# Top.net
KiCad netlist of a schematic drawn in Altium Designer
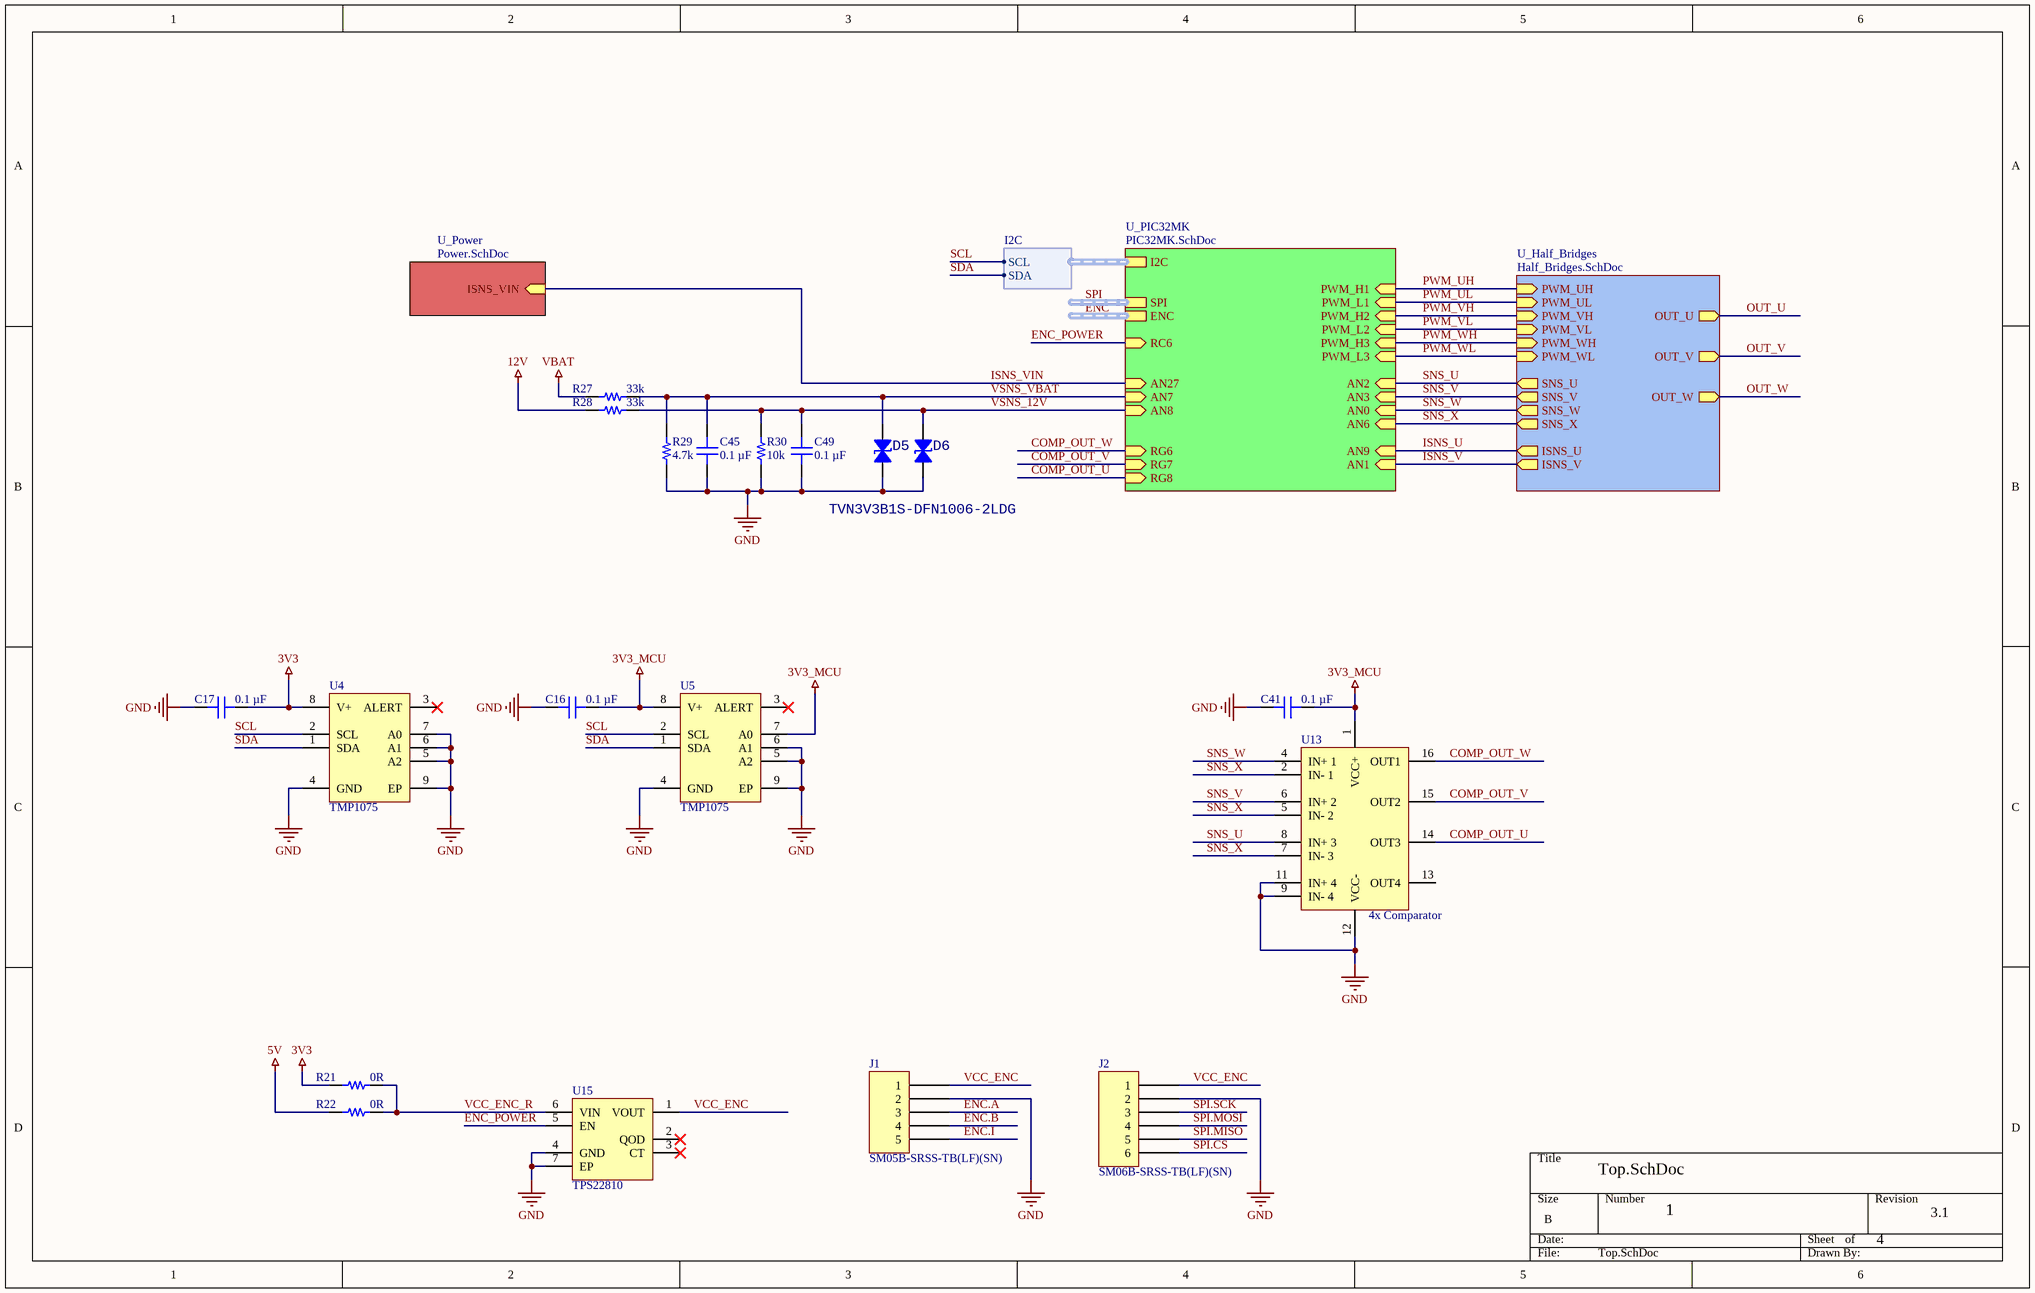
[diagram p0: Top.SchDoc]

(export (version "E")
  (design (tool "Eeschema 10.0.6"))
  (components
    (comp (ref "C16")
      (value "0.1 µF")
      (footprint "CAP 0402_1005")
      (description "CAP CER 0.1UF 16V X7R 0402")
      (fields (field (name "PART NUMBER") "C0402C104K4RACAUTO") (field (name "MANUFACTURER") "KEMET"))
      (libsource (lib "Celestial Altium Library - altium_library") (part "Capacitor"))
    )
    (comp (ref "C17")
      (value "0.1 µF")
      (footprint "CAP 0402_1005")
      (description "CAP CER 0.1UF 16V X7R 0402")
      (fields (field (name "PART NUMBER") "C0402C104K4RACAUTO") (field (name "MANUFACTURER") "KEMET"))
      (libsource (lib "Celestial Altium Library - altium_library") (part "Capacitor"))
    )
    (comp (ref "C41")
      (value "0.1 µF")
      (footprint "CAP 0402_1005")
      (description "CAP CER 0.1UF 16V X7R 0402")
      (fields (field (name "PART NUMBER") "C0402C104K4RACAUTO") (field (name "MANUFACTURER") "KEMET"))
      (libsource (lib "Celestial Altium Library - altium_library") (part "Capacitor"))
    )
    (comp (ref "C45")
      (value "0.1 µF")
      (footprint "CAP 0402_1005")
      (description "CAP CER 0.1UF 16V X7R 0402")
      (fields (field (name "PART NUMBER") "C0402C104K4RACAUTO") (field (name "MANUFACTURER") "KEMET"))
      (libsource (lib "Celestial Altium Library - altium_library") (part "Capacitor"))
    )
    (comp (ref "C49")
      (value "0.1 µF")
      (footprint "CAP 0402_1005")
      (description "CAP CER 0.1UF 16V X7R 0402")
      (fields (field (name "PART NUMBER") "C0402C104K4RACAUTO") (field (name "MANUFACTURER") "KEMET"))
      (libsource (lib "Celestial Altium Library - altium_library") (part "Capacitor"))
    )
    (comp (ref "D5")
      (value "TVN3V3B1S-DFN1006-2LDG")
      (footprint "0402")
      (description "TVS DIODE 3.3V 14.2PF DFN1006")
      (fields (field (name "MANUFACTURER") "INPAQ Technology Co., Ltd"))
      (libsource (lib "Celestial Altium Library - altium_library") (part "Diode TVS"))
    )
    (comp (ref "D6")
      (value "TVN3V3B1S-DFN1006-2LDG")
      (footprint "0402")
      (description "TVS DIODE 3.3V 14.2PF DFN1006")
      (fields (field (name "MANUFACTURER") "INPAQ Technology Co., Ltd"))
      (libsource (lib "Celestial Altium Library - altium_library") (part "Diode TVS"))
    )
    (comp (ref "J1")
      (value "SM05B-SRSS-TB(LF)(SN)")
      (footprint "JST SM05B-SRSS-TB")
      (description "CONN HEADER SMD R/A 5POS 1MM")
      (fields (field (name "MANUFACTURER") "JST Sales America Inc."))
      (libsource (lib "Celestial Altium Library - altium_library") (part "5 Pin"))
    )
    (comp (ref "J2")
      (value "SM06B-SRSS-TB(LF)(SN)")
      (footprint "JST SM06B-SRSS-TB")
      (description "CONN HEADER SMD R/A 6POS 1MM")
      (fields (field (name "MANUFACTURER") "JST Sales America Inc."))
      (libsource (lib "Celestial Altium Library - altium_library") (part "6 Pin"))
    )
    (comp (ref "R21")
      (value "0R")
      (footprint "RES_0402")
      (description "RES 0402")
      (libsource (lib "IC") (part "RES_0402"))
    )
    (comp (ref "R22")
      (value "0R")
      (footprint "RES_0402")
      (description "RES 0402")
      (libsource (lib "IC") (part "RES_0402"))
    )
    (comp (ref "R27")
      (value "33k")
      (footprint "RES_0402")
      (description "RES 0402")
      (libsource (lib "IC") (part "RES_0402"))
    )
    (comp (ref "R28")
      (value "33k")
      (footprint "RES_0402")
      (description "RES 0402")
      (libsource (lib "IC") (part "RES_0402"))
    )
    (comp (ref "R29")
      (value "4.7k")
      (footprint "RES_0402")
      (description "RES 0402")
      (libsource (lib "IC") (part "RES_0402"))
    )
    (comp (ref "R30")
      (value "10k")
      (footprint "RES_0402")
      (description "RES 0402")
      (libsource (lib "IC") (part "RES_0402"))
    )
    (comp (ref "U4")
      (value "TMP1075")
      (footprint "8_WSON_2x2_0.5mm")
      (description "I2C TEMP SENSOR")
      (libsource (lib "IC") (part "TMP1075"))
    )
    (comp (ref "U5")
      (value "TMP1075")
      (footprint "8_WSON_2x2_0.5mm")
      (description "I2C TEMP SENSOR")
      (libsource (lib "IC") (part "TMP1075"))
    )
    (comp (ref "U13")
      (value "4x Comparator")
      (footprint "QFN50P300X300X100-16N")
      (description "Comparator General Purpose CMOS, DTL, MOS, Open-Collector, TTL 16-QFN (3x3)")
      (libsource (lib "IC") (part "LM2901Q4T"))
    )
    (comp (ref "U15")
      (value "TPS22810")
      (footprint "6-WSON_2x2_0.65mm")
      (description "Load switch TPS22810DRVR")
      (libsource (lib "IC") (part "TPS22810DRVR"))
    )
  )
  (nets
    (net (code "4") (name "/COMP_OUT_U") (class "Default")
      (node (ref "U13") (pin "14") (pinfunction "OUT3_14") (pintype "passive"))
    )
    (net (code "5") (name "/COMP_OUT_V") (class "Default")
      (node (ref "U13") (pin "15") (pinfunction "OUT2_15") (pintype "passive"))
    )
    (net (code "6") (name "/COMP_OUT_W") (class "Default")
      (node (ref "U13") (pin "16") (pinfunction "OUT1_16") (pintype "passive"))
    )
    (net (code "7") (name "/ENC.A") (class "Default")
      (node (ref "J1") (pin "3") (pinfunction "3_3") (pintype "passive"))
    )
    (net (code "8") (name "/ENC.B") (class "Default")
      (node (ref "J1") (pin "4") (pinfunction "4_4") (pintype "passive"))
    )
    (net (code "9") (name "/ENC.I") (class "Default")
      (node (ref "J1") (pin "5") (pinfunction "5_5") (pintype "passive"))
    )
    (net (code "10") (name "/ENC_POWER") (class "Default")
      (node (ref "U15") (pin "5") (pinfunction "EN_5") (pintype "passive"))
    )
    (net (code "23") (name "/SCL") (class "Default")
      (node (ref "U4") (pin "2") (pinfunction "SCL_2") (pintype "passive"))
      (node (ref "U5") (pin "2") (pinfunction "SCL_2") (pintype "passive"))
    )
    (net (code "24") (name "/SDA") (class "Default")
      (node (ref "U4") (pin "1") (pinfunction "SDA_1") (pintype "passive"))
      (node (ref "U5") (pin "1") (pinfunction "SDA_1") (pintype "passive"))
    )
    (net (code "25") (name "/SNS_U") (class "Default")
      (node (ref "U13") (pin "8") (pinfunction "IN+_3_8") (pintype "passive"))
    )
    (net (code "26") (name "/SNS_V") (class "Default")
      (node (ref "U13") (pin "6") (pinfunction "IN+_2_6") (pintype "passive"))
    )
    (net (code "27") (name "/SNS_W") (class "Default")
      (node (ref "U13") (pin "4") (pinfunction "IN+_1_4") (pintype "passive"))
    )
    (net (code "28") (name "/SNS_X") (class "Default")
      (node (ref "U13") (pin "2") (pinfunction "IN-_1_2") (pintype "passive"))
      (node (ref "U13") (pin "5") (pinfunction "IN-_2_5") (pintype "passive"))
      (node (ref "U13") (pin "7") (pinfunction "IN-_3_7") (pintype "passive"))
    )
    (net (code "29") (name "/SPI.MISO") (class "Default")
      (node (ref "J2") (pin "5") (pinfunction "5_5") (pintype "passive"))
    )
    (net (code "30") (name "/SPI.MOSI") (class "Default")
      (node (ref "J2") (pin "4") (pinfunction "4_4") (pintype "passive"))
    )
    (net (code "31") (name "/SPI.SCK") (class "Default")
      (node (ref "J2") (pin "3") (pinfunction "3_3") (pintype "passive"))
    )
    (net (code "32") (name "/SPI.~{CS}") (class "Default")
      (node (ref "J2") (pin "6") (pinfunction "6_6") (pintype "passive"))
    )
    (net (code "33") (name "/VCC_ENC") (class "Default")
      (node (ref "J1") (pin "1") (pinfunction "1_1") (pintype "passive"))
      (node (ref "J2") (pin "1") (pinfunction "1_1") (pintype "passive"))
      (node (ref "U15") (pin "1") (pinfunction "VOUT_1") (pintype "passive"))
    )
    (net (code "34") (name "/VCC_ENC_R") (class "Default")
      (node (ref "R21") (pin "1") (pinfunction "1_1") (pintype "passive"))
      (node (ref "R22") (pin "1") (pinfunction "1_1") (pintype "passive"))
      (node (ref "U15") (pin "6") (pinfunction "VIN_6") (pintype "passive"))
    )
    (net (code "35") (name "/VSNS_12V") (class "Default")
      (node (ref "C49") (pin "2") (pinfunction "2_2") (pintype "passive"))
      (node (ref "D6") (pin "2") (pinfunction "2_2") (pintype "passive"))
      (node (ref "R28") (pin "1") (pinfunction "1_1") (pintype "passive"))
      (node (ref "R30") (pin "1") (pinfunction "1_1") (pintype "passive"))
    )
    (net (code "36") (name "/VSNS_VBAT") (class "Default")
      (node (ref "C45") (pin "2") (pinfunction "2_2") (pintype "passive"))
      (node (ref "D5") (pin "2") (pinfunction "2_2") (pintype "passive"))
      (node (ref "R27") (pin "1") (pinfunction "1_1") (pintype "passive"))
      (node (ref "R29") (pin "1") (pinfunction "1_1") (pintype "passive"))
    )
    (net (code "40") (name "3V3") (class "Default")
      (node (ref "C17") (pin "2") (pinfunction "2_2") (pintype "passive"))
      (node (ref "R21") (pin "2") (pinfunction "2_2") (pintype "passive"))
      (node (ref "U4") (pin "8") (pinfunction "V+_8") (pintype "passive"))
    )
    (net (code "41") (name "3V3_MCU") (class "Default")
      (node (ref "C16") (pin "2") (pinfunction "2_2") (pintype "passive"))
      (node (ref "C41") (pin "2") (pinfunction "2_2") (pintype "passive"))
      (node (ref "U13") (pin "1") (pinfunction "VCC+_1") (pintype "passive"))
      (node (ref "U5") (pin "7") (pinfunction "A0_7") (pintype "passive"))
      (node (ref "U5") (pin "8") (pinfunction "V+_8") (pintype "passive"))
    )
    (net (code "42") (name "5V") (class "Default")
      (node (ref "R22") (pin "2") (pinfunction "2_2") (pintype "passive"))
    )
    (net (code "43") (name "12V") (class "Default")
      (node (ref "R28") (pin "2") (pinfunction "2_2") (pintype "passive"))
    )
    (net (code "44") (name "GND") (class "Default")
      (node (ref "C16") (pin "1") (pinfunction "1_1") (pintype "passive"))
      (node (ref "C17") (pin "1") (pinfunction "1_1") (pintype "passive"))
      (node (ref "C41") (pin "1") (pinfunction "1_1") (pintype "passive"))
      (node (ref "C45") (pin "1") (pinfunction "1_1") (pintype "passive"))
      (node (ref "C49") (pin "1") (pinfunction "1_1") (pintype "passive"))
      (node (ref "D5") (pin "1") (pinfunction "1_1") (pintype "passive"))
      (node (ref "D6") (pin "1") (pinfunction "1_1") (pintype "passive"))
      (node (ref "J1") (pin "2") (pinfunction "2_2") (pintype "passive"))
      (node (ref "J2") (pin "2") (pinfunction "2_2") (pintype "passive"))
      (node (ref "R29") (pin "2") (pinfunction "2_2") (pintype "passive"))
      (node (ref "R30") (pin "2") (pinfunction "2_2") (pintype "passive"))
      (node (ref "U13") (pin "11") (pinfunction "IN+_4_11") (pintype "passive"))
      (node (ref "U13") (pin "12") (pinfunction "VCC-_12") (pintype "passive"))
      (node (ref "U13") (pin "9") (pinfunction "IN-_4_9") (pintype "passive"))
      (node (ref "U15") (pin "4") (pinfunction "GND_4") (pintype "passive"))
      (node (ref "U15") (pin "7") (pinfunction "EP_7") (pintype "passive"))
      (node (ref "U4") (pin "4") (pinfunction "GND_4") (pintype "passive"))
      (node (ref "U4") (pin "5") (pinfunction "A2_5") (pintype "passive"))
      (node (ref "U4") (pin "6") (pinfunction "A1_6") (pintype "passive"))
      (node (ref "U4") (pin "7") (pinfunction "A0_7") (pintype "passive"))
      (node (ref "U4") (pin "9") (pinfunction "EP_9") (pintype "passive"))
      (node (ref "U5") (pin "4") (pinfunction "GND_4") (pintype "passive"))
      (node (ref "U5") (pin "5") (pinfunction "A2_5") (pintype "passive"))
      (node (ref "U5") (pin "6") (pinfunction "A1_6") (pintype "passive"))
      (node (ref "U5") (pin "9") (pinfunction "EP_9") (pintype "passive"))
    )
    (net (code "45") (name "VBAT") (class "Default")
      (node (ref "R27") (pin "2") (pinfunction "2_2") (pintype "passive"))
    )
    (net (code "46") (name "unconnected-(U4-ALERT-Pad3)") (class "Default")
      (node (ref "U4") (pin "3") (pinfunction "ALERT_3") (pintype "passive+no_connect"))
    )
    (net (code "47") (name "unconnected-(U5-ALERT-Pad3)") (class "Default")
      (node (ref "U5") (pin "3") (pinfunction "ALERT_3") (pintype "passive+no_connect"))
    )
    (net (code "48") (name "unconnected-(U13-OUT4-Pad13)") (class "Default")
      (node (ref "U13") (pin "13") (pinfunction "OUT4_13") (pintype "passive"))
    )
    (net (code "49") (name "unconnected-(U15-CT-Pad3)") (class "Default")
      (node (ref "U15") (pin "3") (pinfunction "CT_3") (pintype "passive+no_connect"))
    )
    (net (code "50") (name "unconnected-(U15-QOD-Pad2)") (class "Default")
      (node (ref "U15") (pin "2") (pinfunction "QOD_2") (pintype "passive+no_connect"))
    )
  )
)
